# LED_STRIP.net
KiCad netlist of a schematic drawn in EAGLE
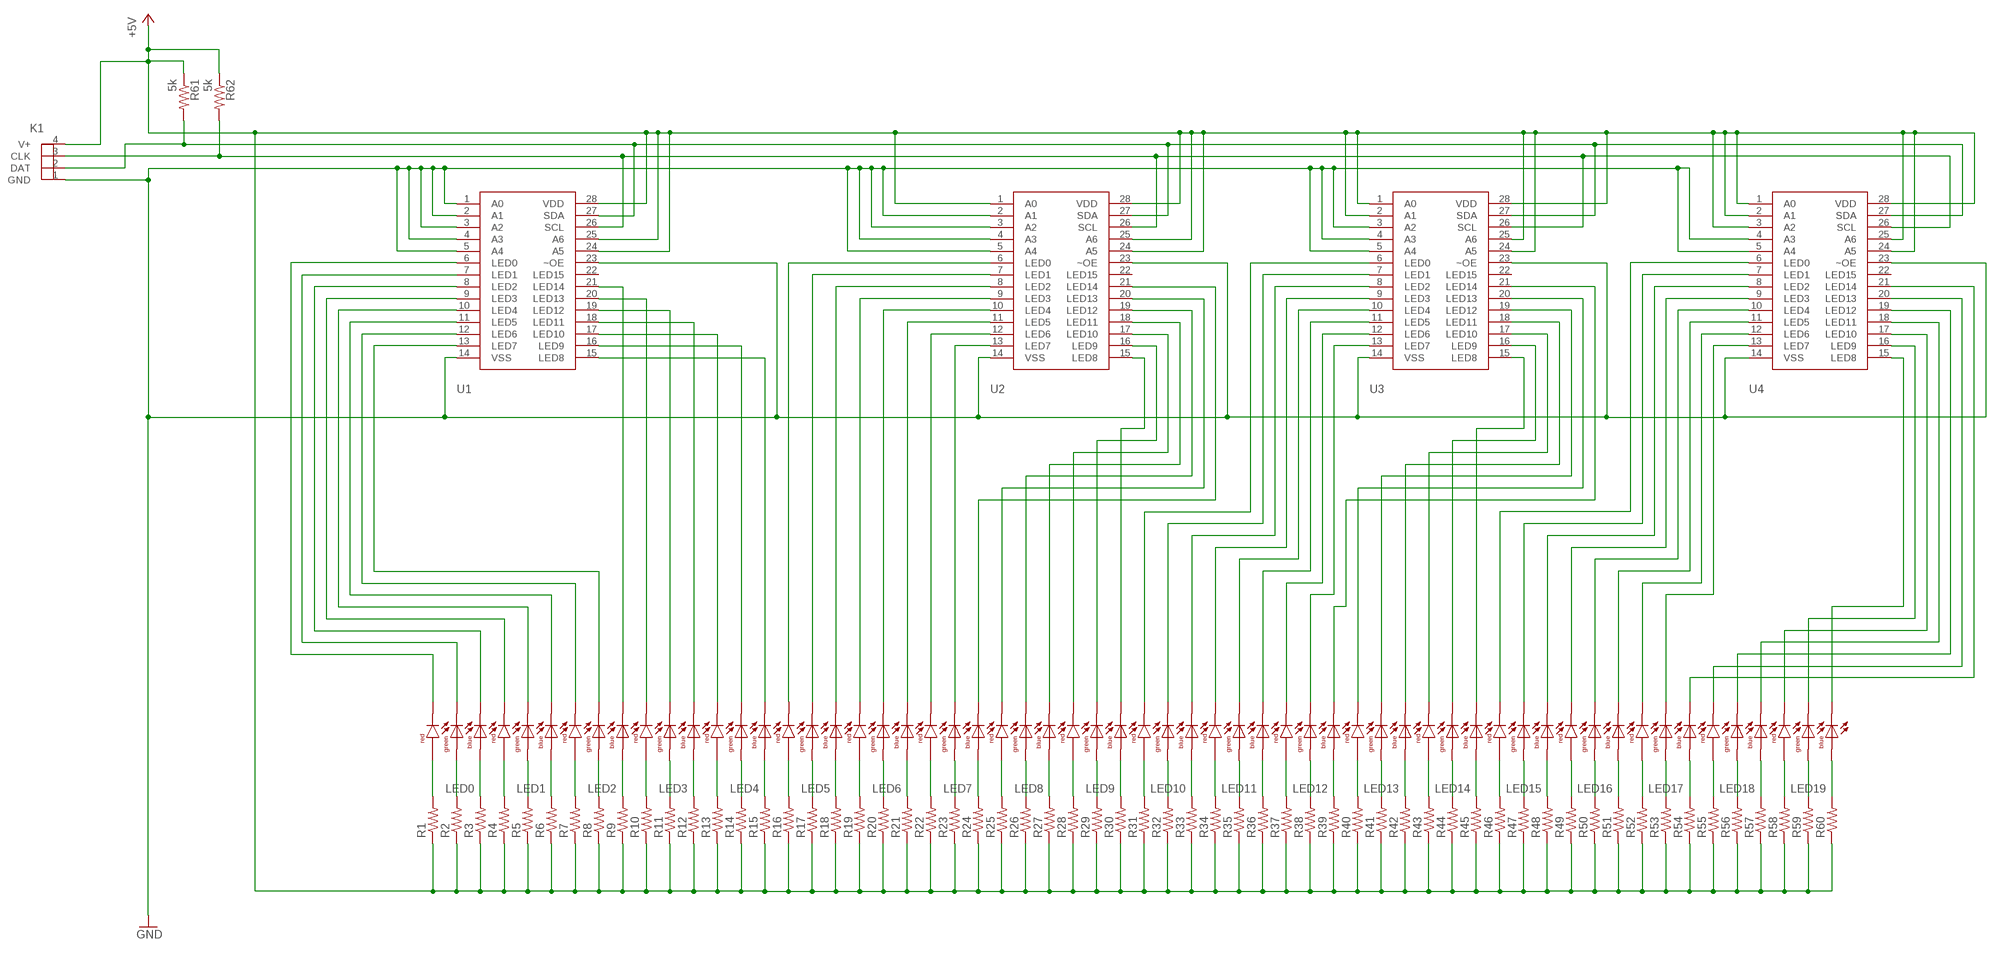
[diagram p0: schematic, sheet 1]

(export (version "E")
  (design (tool "Eeschema 10.0.6"))
  (components
    (comp (ref "K1")
      (value "LEDCONN")
      (footprint "eagle-import:4CONN")
      (libsource (lib "eagle-import") (part "LEDCONN"))
    )
    (comp (ref "LED0")
      (value "LED_RGB")
      (footprint "eagle-import:6-PLCC")
      (libsource (lib "eagle-import") (part "LED_RGB"))
    )
    (comp (ref "LED1")
      (value "LED_RGB")
      (footprint "eagle-import:6-PLCC")
      (libsource (lib "eagle-import") (part "LED_RGB"))
    )
    (comp (ref "LED2")
      (value "LED_RGB")
      (footprint "eagle-import:6-PLCC")
      (libsource (lib "eagle-import") (part "LED_RGB"))
    )
    (comp (ref "LED3")
      (value "LED_RGB")
      (footprint "eagle-import:6-PLCC")
      (libsource (lib "eagle-import") (part "LED_RGB"))
    )
    (comp (ref "LED4")
      (value "LED_RGB")
      (footprint "eagle-import:6-PLCC")
      (libsource (lib "eagle-import") (part "LED_RGB"))
    )
    (comp (ref "LED5")
      (value "LED_RGB")
      (footprint "eagle-import:6-PLCC")
      (libsource (lib "eagle-import") (part "LED_RGB"))
    )
    (comp (ref "LED6")
      (value "LED_RGB")
      (footprint "eagle-import:6-PLCC")
      (libsource (lib "eagle-import") (part "LED_RGB"))
    )
    (comp (ref "LED7")
      (value "LED_RGB")
      (footprint "eagle-import:6-PLCC")
      (libsource (lib "eagle-import") (part "LED_RGB"))
    )
    (comp (ref "LED8")
      (value "LED_RGB")
      (footprint "eagle-import:6-PLCC")
      (libsource (lib "eagle-import") (part "LED_RGB"))
    )
    (comp (ref "LED9")
      (value "LED_RGB")
      (footprint "eagle-import:6-PLCC")
      (libsource (lib "eagle-import") (part "LED_RGB"))
    )
    (comp (ref "LED10")
      (value "LED_RGB")
      (footprint "eagle-import:6-PLCC")
      (libsource (lib "eagle-import") (part "LED_RGB"))
    )
    (comp (ref "LED11")
      (value "LED_RGB")
      (footprint "eagle-import:6-PLCC")
      (libsource (lib "eagle-import") (part "LED_RGB"))
    )
    (comp (ref "LED12")
      (value "LED_RGB")
      (footprint "eagle-import:6-PLCC")
      (libsource (lib "eagle-import") (part "LED_RGB"))
    )
    (comp (ref "LED13")
      (value "LED_RGB")
      (footprint "eagle-import:6-PLCC")
      (libsource (lib "eagle-import") (part "LED_RGB"))
    )
    (comp (ref "LED14")
      (value "LED_RGB")
      (footprint "eagle-import:6-PLCC")
      (libsource (lib "eagle-import") (part "LED_RGB"))
    )
    (comp (ref "LED15")
      (value "LED_RGB")
      (footprint "eagle-import:6-PLCC")
      (libsource (lib "eagle-import") (part "LED_RGB"))
    )
    (comp (ref "LED16")
      (value "LED_RGB")
      (footprint "eagle-import:6-PLCC")
      (libsource (lib "eagle-import") (part "LED_RGB"))
    )
    (comp (ref "LED17")
      (value "LED_RGB")
      (footprint "eagle-import:6-PLCC")
      (libsource (lib "eagle-import") (part "LED_RGB"))
    )
    (comp (ref "LED18")
      (value "LED_RGB")
      (footprint "eagle-import:6-PLCC")
      (libsource (lib "eagle-import") (part "LED_RGB"))
    )
    (comp (ref "LED19")
      (value "LED_RGB")
      (footprint "eagle-import:6-PLCC")
      (libsource (lib "eagle-import") (part "LED_RGB"))
    )
    (comp (ref "R1")
      (value "R0402")
      (footprint "eagle-import:0402")
      (libsource (lib "eagle-import") (part "R0402"))
    )
    (comp (ref "R2")
      (value "R0402")
      (footprint "eagle-import:0402")
      (libsource (lib "eagle-import") (part "R0402"))
    )
    (comp (ref "R3")
      (value "R0402")
      (footprint "eagle-import:0402")
      (libsource (lib "eagle-import") (part "R0402"))
    )
    (comp (ref "R4")
      (value "R0402")
      (footprint "eagle-import:0402")
      (libsource (lib "eagle-import") (part "R0402"))
    )
    (comp (ref "R5")
      (value "R0402")
      (footprint "eagle-import:0402")
      (libsource (lib "eagle-import") (part "R0402"))
    )
    (comp (ref "R6")
      (value "R0402")
      (footprint "eagle-import:0402")
      (libsource (lib "eagle-import") (part "R0402"))
    )
    (comp (ref "R7")
      (value "R0402")
      (footprint "eagle-import:0402")
      (libsource (lib "eagle-import") (part "R0402"))
    )
    (comp (ref "R8")
      (value "R0402")
      (footprint "eagle-import:0402")
      (libsource (lib "eagle-import") (part "R0402"))
    )
    (comp (ref "R9")
      (value "R0402")
      (footprint "eagle-import:0402")
      (libsource (lib "eagle-import") (part "R0402"))
    )
    (comp (ref "R10")
      (value "R0402")
      (footprint "eagle-import:0402")
      (libsource (lib "eagle-import") (part "R0402"))
    )
    (comp (ref "R11")
      (value "R0402")
      (footprint "eagle-import:0402")
      (libsource (lib "eagle-import") (part "R0402"))
    )
    (comp (ref "R12")
      (value "R0402")
      (footprint "eagle-import:0402")
      (libsource (lib "eagle-import") (part "R0402"))
    )
    (comp (ref "R13")
      (value "R0402")
      (footprint "eagle-import:0402")
      (libsource (lib "eagle-import") (part "R0402"))
    )
    (comp (ref "R14")
      (value "R0402")
      (footprint "eagle-import:0402")
      (libsource (lib "eagle-import") (part "R0402"))
    )
    (comp (ref "R15")
      (value "R0402")
      (footprint "eagle-import:0402")
      (libsource (lib "eagle-import") (part "R0402"))
    )
    (comp (ref "R16")
      (value "R0402")
      (footprint "eagle-import:0402")
      (libsource (lib "eagle-import") (part "R0402"))
    )
    (comp (ref "R17")
      (value "R0402")
      (footprint "eagle-import:0402")
      (libsource (lib "eagle-import") (part "R0402"))
    )
    (comp (ref "R18")
      (value "R0402")
      (footprint "eagle-import:0402")
      (libsource (lib "eagle-import") (part "R0402"))
    )
    (comp (ref "R19")
      (value "R0402")
      (footprint "eagle-import:0402")
      (libsource (lib "eagle-import") (part "R0402"))
    )
    (comp (ref "R20")
      (value "R0402")
      (footprint "eagle-import:0402")
      (libsource (lib "eagle-import") (part "R0402"))
    )
    (comp (ref "R21")
      (value "R0402")
      (footprint "eagle-import:0402")
      (libsource (lib "eagle-import") (part "R0402"))
    )
    (comp (ref "R22")
      (value "R0402")
      (footprint "eagle-import:0402")
      (libsource (lib "eagle-import") (part "R0402"))
    )
    (comp (ref "R23")
      (value "R0402")
      (footprint "eagle-import:0402")
      (libsource (lib "eagle-import") (part "R0402"))
    )
    (comp (ref "R24")
      (value "R0402")
      (footprint "eagle-import:0402")
      (libsource (lib "eagle-import") (part "R0402"))
    )
    (comp (ref "R25")
      (value "R0402")
      (footprint "eagle-import:0402")
      (libsource (lib "eagle-import") (part "R0402"))
    )
    (comp (ref "R26")
      (value "R0402")
      (footprint "eagle-import:0402")
      (libsource (lib "eagle-import") (part "R0402"))
    )
    (comp (ref "R27")
      (value "R0402")
      (footprint "eagle-import:0402")
      (libsource (lib "eagle-import") (part "R0402"))
    )
    (comp (ref "R28")
      (value "R0402")
      (footprint "eagle-import:0402")
      (libsource (lib "eagle-import") (part "R0402"))
    )
    (comp (ref "R29")
      (value "R0402")
      (footprint "eagle-import:0402")
      (libsource (lib "eagle-import") (part "R0402"))
    )
    (comp (ref "R30")
      (value "R0402")
      (footprint "eagle-import:0402")
      (libsource (lib "eagle-import") (part "R0402"))
    )
    (comp (ref "R31")
      (value "R0402")
      (footprint "eagle-import:0402")
      (libsource (lib "eagle-import") (part "R0402"))
    )
    (comp (ref "R32")
      (value "R0402")
      (footprint "eagle-import:0402")
      (libsource (lib "eagle-import") (part "R0402"))
    )
    (comp (ref "R33")
      (value "R0402")
      (footprint "eagle-import:0402")
      (libsource (lib "eagle-import") (part "R0402"))
    )
    (comp (ref "R34")
      (value "R0402")
      (footprint "eagle-import:0402")
      (libsource (lib "eagle-import") (part "R0402"))
    )
    (comp (ref "R35")
      (value "R0402")
      (footprint "eagle-import:0402")
      (libsource (lib "eagle-import") (part "R0402"))
    )
    (comp (ref "R36")
      (value "R0402")
      (footprint "eagle-import:0402")
      (libsource (lib "eagle-import") (part "R0402"))
    )
    (comp (ref "R37")
      (value "R0402")
      (footprint "eagle-import:0402")
      (libsource (lib "eagle-import") (part "R0402"))
    )
    (comp (ref "R38")
      (value "R0402")
      (footprint "eagle-import:0402")
      (libsource (lib "eagle-import") (part "R0402"))
    )
    (comp (ref "R39")
      (value "R0402")
      (footprint "eagle-import:0402")
      (libsource (lib "eagle-import") (part "R0402"))
    )
    (comp (ref "R40")
      (value "R0402")
      (footprint "eagle-import:0402")
      (libsource (lib "eagle-import") (part "R0402"))
    )
    (comp (ref "R41")
      (value "R0402")
      (footprint "eagle-import:0402")
      (libsource (lib "eagle-import") (part "R0402"))
    )
    (comp (ref "R42")
      (value "R0402")
      (footprint "eagle-import:0402")
      (libsource (lib "eagle-import") (part "R0402"))
    )
    (comp (ref "R43")
      (value "R0402")
      (footprint "eagle-import:0402")
      (libsource (lib "eagle-import") (part "R0402"))
    )
    (comp (ref "R44")
      (value "R0402")
      (footprint "eagle-import:0402")
      (libsource (lib "eagle-import") (part "R0402"))
    )
    (comp (ref "R45")
      (value "R0402")
      (footprint "eagle-import:0402")
      (libsource (lib "eagle-import") (part "R0402"))
    )
    (comp (ref "R46")
      (value "R0402")
      (footprint "eagle-import:0402")
      (libsource (lib "eagle-import") (part "R0402"))
    )
    (comp (ref "R47")
      (value "R0402")
      (footprint "eagle-import:0402")
      (libsource (lib "eagle-import") (part "R0402"))
    )
    (comp (ref "R48")
      (value "R0402")
      (footprint "eagle-import:0402")
      (libsource (lib "eagle-import") (part "R0402"))
    )
    (comp (ref "R49")
      (value "R0402")
      (footprint "eagle-import:0402")
      (libsource (lib "eagle-import") (part "R0402"))
    )
    (comp (ref "R50")
      (value "R0402")
      (footprint "eagle-import:0402")
      (libsource (lib "eagle-import") (part "R0402"))
    )
    (comp (ref "R51")
      (value "R0402")
      (footprint "eagle-import:0402")
      (libsource (lib "eagle-import") (part "R0402"))
    )
    (comp (ref "R52")
      (value "R0402")
      (footprint "eagle-import:0402")
      (libsource (lib "eagle-import") (part "R0402"))
    )
    (comp (ref "R53")
      (value "R0402")
      (footprint "eagle-import:0402")
      (libsource (lib "eagle-import") (part "R0402"))
    )
    (comp (ref "R54")
      (value "R0402")
      (footprint "eagle-import:0402")
      (libsource (lib "eagle-import") (part "R0402"))
    )
    (comp (ref "R55")
      (value "R0402")
      (footprint "eagle-import:0402")
      (libsource (lib "eagle-import") (part "R0402"))
    )
    (comp (ref "R56")
      (value "R0402")
      (footprint "eagle-import:0402")
      (libsource (lib "eagle-import") (part "R0402"))
    )
    (comp (ref "R57")
      (value "R0402")
      (footprint "eagle-import:0402")
      (libsource (lib "eagle-import") (part "R0402"))
    )
    (comp (ref "R58")
      (value "R0402")
      (footprint "eagle-import:0402")
      (libsource (lib "eagle-import") (part "R0402"))
    )
    (comp (ref "R59")
      (value "R0402")
      (footprint "eagle-import:0402")
      (libsource (lib "eagle-import") (part "R0402"))
    )
    (comp (ref "R60")
      (value "R0402")
      (footprint "eagle-import:0402")
      (libsource (lib "eagle-import") (part "R0402"))
    )
    (comp (ref "R61")
      (value "5k")
      (footprint "eagle-import:0402")
      (libsource (lib "eagle-import") (part "R0402"))
    )
    (comp (ref "R62")
      (value "5k")
      (footprint "eagle-import:0402")
      (libsource (lib "eagle-import") (part "R0402"))
    )
    (comp (ref "U1")
      (value "PCA9635")
      (footprint "eagle-import:TSSOP28")
      (libsource (lib "eagle-import") (part "PCA9635"))
    )
    (comp (ref "U2")
      (value "PCA9635")
      (footprint "eagle-import:TSSOP28")
      (libsource (lib "eagle-import") (part "PCA9635"))
    )
    (comp (ref "U3")
      (value "PCA9635")
      (footprint "eagle-import:TSSOP28")
      (libsource (lib "eagle-import") (part "PCA9635"))
    )
    (comp (ref "U4")
      (value "PCA9635")
      (footprint "eagle-import:TSSOP28")
      (libsource (lib "eagle-import") (part "PCA9635"))
    )
  )
  (nets
    (net (code "1") (name "+5V") (class "Default")
      (node (ref "K1") (pin "4") (pinfunction "V+_4") (pintype "bidirectional"))
      (node (ref "R1") (pin "P$1") (pinfunction "1_P$1") (pintype "passive"))
      (node (ref "R10") (pin "P$1") (pinfunction "1_P$1") (pintype "passive"))
      (node (ref "R11") (pin "P$1") (pinfunction "1_P$1") (pintype "passive"))
      (node (ref "R12") (pin "P$1") (pinfunction "1_P$1") (pintype "passive"))
      (node (ref "R13") (pin "P$1") (pinfunction "1_P$1") (pintype "passive"))
      (node (ref "R14") (pin "P$1") (pinfunction "1_P$1") (pintype "passive"))
      (node (ref "R15") (pin "P$1") (pinfunction "1_P$1") (pintype "passive"))
      (node (ref "R16") (pin "P$1") (pinfunction "1_P$1") (pintype "passive"))
      (node (ref "R17") (pin "P$1") (pinfunction "1_P$1") (pintype "passive"))
      (node (ref "R18") (pin "P$1") (pinfunction "1_P$1") (pintype "passive"))
      (node (ref "R19") (pin "P$1") (pinfunction "1_P$1") (pintype "passive"))
      (node (ref "R2") (pin "P$1") (pinfunction "1_P$1") (pintype "passive"))
      (node (ref "R20") (pin "P$1") (pinfunction "1_P$1") (pintype "passive"))
      (node (ref "R21") (pin "P$1") (pinfunction "1_P$1") (pintype "passive"))
      (node (ref "R22") (pin "P$1") (pinfunction "1_P$1") (pintype "passive"))
      (node (ref "R23") (pin "P$1") (pinfunction "1_P$1") (pintype "passive"))
      (node (ref "R24") (pin "P$1") (pinfunction "1_P$1") (pintype "passive"))
      (node (ref "R25") (pin "P$1") (pinfunction "1_P$1") (pintype "passive"))
      (node (ref "R26") (pin "P$1") (pinfunction "1_P$1") (pintype "passive"))
      (node (ref "R27") (pin "P$1") (pinfunction "1_P$1") (pintype "passive"))
      (node (ref "R28") (pin "P$1") (pinfunction "1_P$1") (pintype "passive"))
      (node (ref "R29") (pin "P$1") (pinfunction "1_P$1") (pintype "passive"))
      (node (ref "R3") (pin "P$1") (pinfunction "1_P$1") (pintype "passive"))
      (node (ref "R30") (pin "P$1") (pinfunction "1_P$1") (pintype "passive"))
      (node (ref "R31") (pin "P$1") (pinfunction "1_P$1") (pintype "passive"))
      (node (ref "R32") (pin "P$1") (pinfunction "1_P$1") (pintype "passive"))
      (node (ref "R33") (pin "P$1") (pinfunction "1_P$1") (pintype "passive"))
      (node (ref "R34") (pin "P$1") (pinfunction "1_P$1") (pintype "passive"))
      (node (ref "R35") (pin "P$1") (pinfunction "1_P$1") (pintype "passive"))
      (node (ref "R36") (pin "P$1") (pinfunction "1_P$1") (pintype "passive"))
      (node (ref "R37") (pin "P$1") (pinfunction "1_P$1") (pintype "passive"))
      (node (ref "R38") (pin "P$1") (pinfunction "1_P$1") (pintype "passive"))
      (node (ref "R39") (pin "P$1") (pinfunction "1_P$1") (pintype "passive"))
      (node (ref "R4") (pin "P$1") (pinfunction "1_P$1") (pintype "passive"))
      (node (ref "R40") (pin "P$1") (pinfunction "1_P$1") (pintype "passive"))
      (node (ref "R41") (pin "P$1") (pinfunction "1_P$1") (pintype "passive"))
      (node (ref "R42") (pin "P$1") (pinfunction "1_P$1") (pintype "passive"))
      (node (ref "R43") (pin "P$1") (pinfunction "1_P$1") (pintype "passive"))
      (node (ref "R44") (pin "P$1") (pinfunction "1_P$1") (pintype "passive"))
      (node (ref "R45") (pin "P$1") (pinfunction "1_P$1") (pintype "passive"))
      (node (ref "R46") (pin "P$1") (pinfunction "1_P$1") (pintype "passive"))
      (node (ref "R47") (pin "P$1") (pinfunction "1_P$1") (pintype "passive"))
      (node (ref "R48") (pin "P$1") (pinfunction "1_P$1") (pintype "passive"))
      (node (ref "R49") (pin "P$1") (pinfunction "1_P$1") (pintype "passive"))
      (node (ref "R5") (pin "P$1") (pinfunction "1_P$1") (pintype "passive"))
      (node (ref "R50") (pin "P$1") (pinfunction "1_P$1") (pintype "passive"))
      (node (ref "R51") (pin "P$1") (pinfunction "1_P$1") (pintype "passive"))
      (node (ref "R52") (pin "P$1") (pinfunction "1_P$1") (pintype "passive"))
      (node (ref "R53") (pin "P$1") (pinfunction "1_P$1") (pintype "passive"))
      (node (ref "R54") (pin "P$1") (pinfunction "1_P$1") (pintype "passive"))
      (node (ref "R55") (pin "P$1") (pinfunction "1_P$1") (pintype "passive"))
      (node (ref "R56") (pin "P$1") (pinfunction "1_P$1") (pintype "passive"))
      (node (ref "R57") (pin "P$1") (pinfunction "1_P$1") (pintype "passive"))
      (node (ref "R58") (pin "P$1") (pinfunction "1_P$1") (pintype "passive"))
      (node (ref "R59") (pin "P$1") (pinfunction "1_P$1") (pintype "passive"))
      (node (ref "R6") (pin "P$1") (pinfunction "1_P$1") (pintype "passive"))
      (node (ref "R60") (pin "P$1") (pinfunction "1_P$1") (pintype "passive"))
      (node (ref "R61") (pin "P$1") (pinfunction "1_P$1") (pintype "passive"))
      (node (ref "R62") (pin "P$1") (pinfunction "1_P$1") (pintype "passive"))
      (node (ref "R7") (pin "P$1") (pinfunction "1_P$1") (pintype "passive"))
      (node (ref "R8") (pin "P$1") (pinfunction "1_P$1") (pintype "passive"))
      (node (ref "R9") (pin "P$1") (pinfunction "1_P$1") (pintype "passive"))
      (node (ref "U1") (pin "24") (pinfunction "A5_24") (pintype "bidirectional"))
      (node (ref "U1") (pin "25") (pinfunction "A6_25") (pintype "bidirectional"))
      (node (ref "U1") (pin "28") (pinfunction "VDD_28") (pintype "bidirectional"))
      (node (ref "U2") (pin "1") (pinfunction "A0_1") (pintype "bidirectional"))
      (node (ref "U2") (pin "24") (pinfunction "A5_24") (pintype "bidirectional"))
      (node (ref "U2") (pin "25") (pinfunction "A6_25") (pintype "bidirectional"))
      (node (ref "U2") (pin "28") (pinfunction "VDD_28") (pintype "bidirectional"))
      (node (ref "U3") (pin "1") (pinfunction "A0_1") (pintype "bidirectional"))
      (node (ref "U3") (pin "2") (pinfunction "A1_2") (pintype "bidirectional"))
      (node (ref "U3") (pin "24") (pinfunction "A5_24") (pintype "bidirectional"))
      (node (ref "U3") (pin "25") (pinfunction "A6_25") (pintype "bidirectional"))
      (node (ref "U3") (pin "28") (pinfunction "VDD_28") (pintype "bidirectional"))
      (node (ref "U4") (pin "1") (pinfunction "A0_1") (pintype "bidirectional"))
      (node (ref "U4") (pin "2") (pinfunction "A1_2") (pintype "bidirectional"))
      (node (ref "U4") (pin "24") (pinfunction "A5_24") (pintype "bidirectional"))
      (node (ref "U4") (pin "25") (pinfunction "A6_25") (pintype "bidirectional"))
      (node (ref "U4") (pin "28") (pinfunction "VDD_28") (pintype "bidirectional"))
      (node (ref "U4") (pin "3") (pinfunction "A2_3") (pintype "bidirectional"))
    )
    (net (code "2") (name "GND") (class "Default")
      (node (ref "K1") (pin "1") (pinfunction "GND_1") (pintype "bidirectional"))
      (node (ref "U1") (pin "1") (pinfunction "A0_1") (pintype "bidirectional"))
      (node (ref "U1") (pin "14") (pinfunction "VSS_14") (pintype "bidirectional"))
      (node (ref "U1") (pin "2") (pinfunction "A1_2") (pintype "bidirectional"))
      (node (ref "U1") (pin "23") (pinfunction "~{OE}_23") (pintype "bidirectional"))
      (node (ref "U1") (pin "3") (pinfunction "A2_3") (pintype "bidirectional"))
      (node (ref "U1") (pin "4") (pinfunction "A3_4") (pintype "bidirectional"))
      (node (ref "U1") (pin "5") (pinfunction "A4_5") (pintype "bidirectional"))
      (node (ref "U2") (pin "14") (pinfunction "VSS_14") (pintype "bidirectional"))
      (node (ref "U2") (pin "2") (pinfunction "A1_2") (pintype "bidirectional"))
      (node (ref "U2") (pin "23") (pinfunction "~{OE}_23") (pintype "bidirectional"))
      (node (ref "U2") (pin "3") (pinfunction "A2_3") (pintype "bidirectional"))
      (node (ref "U2") (pin "4") (pinfunction "A3_4") (pintype "bidirectional"))
      (node (ref "U2") (pin "5") (pinfunction "A4_5") (pintype "bidirectional"))
      (node (ref "U3") (pin "14") (pinfunction "VSS_14") (pintype "bidirectional"))
      (node (ref "U3") (pin "23") (pinfunction "~{OE}_23") (pintype "bidirectional"))
      (node (ref "U3") (pin "3") (pinfunction "A2_3") (pintype "bidirectional"))
      (node (ref "U3") (pin "4") (pinfunction "A3_4") (pintype "bidirectional"))
      (node (ref "U3") (pin "5") (pinfunction "A4_5") (pintype "bidirectional"))
      (node (ref "U4") (pin "14") (pinfunction "VSS_14") (pintype "bidirectional"))
      (node (ref "U4") (pin "23") (pinfunction "~{OE}_23") (pintype "bidirectional"))
      (node (ref "U4") (pin "4") (pinfunction "A3_4") (pintype "bidirectional"))
      (node (ref "U4") (pin "5") (pinfunction "A4_5") (pintype "bidirectional"))
    )
    (net (code "3") (name "Net-(K1-CLK)") (class "Default")
      (node (ref "K1") (pin "3") (pinfunction "CLK_3") (pintype "bidirectional"))
      (node (ref "R62") (pin "P$2") (pinfunction "2_P$2") (pintype "passive"))
      (node (ref "U1") (pin "26") (pinfunction "SCL_26") (pintype "bidirectional"))
      (node (ref "U2") (pin "26") (pinfunction "SCL_26") (pintype "bidirectional"))
      (node (ref "U3") (pin "26") (pinfunction "SCL_26") (pintype "bidirectional"))
      (node (ref "U4") (pin "26") (pinfunction "SCL_26") (pintype "bidirectional"))
    )
    (net (code "4") (name "Net-(K1-DAT)") (class "Default")
      (node (ref "K1") (pin "2") (pinfunction "DAT_2") (pintype "bidirectional"))
      (node (ref "R61") (pin "P$2") (pinfunction "2_P$2") (pintype "passive"))
      (node (ref "U1") (pin "27") (pinfunction "SDA_27") (pintype "bidirectional"))
      (node (ref "U2") (pin "27") (pinfunction "SDA_27") (pintype "bidirectional"))
      (node (ref "U3") (pin "27") (pinfunction "SDA_27") (pintype "bidirectional"))
      (node (ref "U4") (pin "27") (pinfunction "SDA_27") (pintype "bidirectional"))
    )
    (net (code "5") (name "Net-(R1-2)") (class "Default")
      (node (ref "LED0") (pin "RED_HIGH") (pinfunction "RED_HIGH_RED_HIGH") (pintype "passive"))
      (node (ref "R1") (pin "P$2") (pinfunction "2_P$2") (pintype "passive"))
    )
    (net (code "6") (name "Net-(R2-2)") (class "Default")
      (node (ref "LED0") (pin "GREEN_HIGH") (pinfunction "GREEN_HIGH_GREEN_HIGH") (pintype "passive"))
      (node (ref "R2") (pin "P$2") (pinfunction "2_P$2") (pintype "passive"))
    )
    (net (code "7") (name "Net-(R3-2)") (class "Default")
      (node (ref "LED0") (pin "BLUE_HIGH") (pinfunction "BLUE_HIGH_BLUE_HIGH") (pintype "passive"))
      (node (ref "R3") (pin "P$2") (pinfunction "2_P$2") (pintype "passive"))
    )
    (net (code "8") (name "Net-(R4-2)") (class "Default")
      (node (ref "LED1") (pin "RED_HIGH") (pinfunction "RED_HIGH_RED_HIGH") (pintype "passive"))
      (node (ref "R4") (pin "P$2") (pinfunction "2_P$2") (pintype "passive"))
    )
    (net (code "9") (name "Net-(R5-2)") (class "Default")
      (node (ref "LED1") (pin "GREEN_HIGH") (pinfunction "GREEN_HIGH_GREEN_HIGH") (pintype "passive"))
      (node (ref "R5") (pin "P$2") (pinfunction "2_P$2") (pintype "passive"))
    )
    (net (code "10") (name "Net-(R6-2)") (class "Default")
      (node (ref "LED1") (pin "BLUE_HIGH") (pinfunction "BLUE_HIGH_BLUE_HIGH") (pintype "passive"))
      (node (ref "R6") (pin "P$2") (pinfunction "2_P$2") (pintype "passive"))
    )
    (net (code "11") (name "Net-(R7-2)") (class "Default")
      (node (ref "LED2") (pin "RED_HIGH") (pinfunction "RED_HIGH_RED_HIGH") (pintype "passive"))
      (node (ref "R7") (pin "P$2") (pinfunction "2_P$2") (pintype "passive"))
    )
    (net (code "12") (name "Net-(R8-2)") (class "Default")
      (node (ref "LED2") (pin "GREEN_HIGH") (pinfunction "GREEN_HIGH_GREEN_HIGH") (pintype "passive"))
      (node (ref "R8") (pin "P$2") (pinfunction "2_P$2") (pintype "passive"))
    )
    (net (code "13") (name "Net-(R9-2)") (class "Default")
      (node (ref "LED2") (pin "BLUE_HIGH") (pinfunction "BLUE_HIGH_BLUE_HIGH") (pintype "passive"))
      (node (ref "R9") (pin "P$2") (pinfunction "2_P$2") (pintype "passive"))
    )
    (net (code "14") (name "Net-(R10-2)") (class "Default")
      (node (ref "LED3") (pin "RED_HIGH") (pinfunction "RED_HIGH_RED_HIGH") (pintype "passive"))
      (node (ref "R10") (pin "P$2") (pinfunction "2_P$2") (pintype "passive"))
    )
    (net (code "15") (name "Net-(R11-2)") (class "Default")
      (node (ref "LED3") (pin "GREEN_HIGH") (pinfunction "GREEN_HIGH_GREEN_HIGH") (pintype "passive"))
      (node (ref "R11") (pin "P$2") (pinfunction "2_P$2") (pintype "passive"))
    )
    (net (code "16") (name "Net-(R12-2)") (class "Default")
      (node (ref "LED3") (pin "BLUE_HIGH") (pinfunction "BLUE_HIGH_BLUE_HIGH") (pintype "passive"))
      (node (ref "R12") (pin "P$2") (pinfunction "2_P$2") (pintype "passive"))
    )
    (net (code "17") (name "Net-(R13-2)") (class "Default")
      (node (ref "LED4") (pin "RED_HIGH") (pinfunction "RED_HIGH_RED_HIGH") (pintype "passive"))
      (node (ref "R13") (pin "P$2") (pinfunction "2_P$2") (pintype "passive"))
    )
    (net (code "18") (name "Net-(R14-2)") (class "Default")
      (node (ref "LED4") (pin "GREEN_HIGH") (pinfunction "GREEN_HIGH_GREEN_HIGH") (pintype "passive"))
      (node (ref "R14") (pin "P$2") (pinfunction "2_P$2") (pintype "passive"))
    )
    (net (code "19") (name "Net-(R15-2)") (class "Default")
      (node (ref "LED4") (pin "BLUE_HIGH") (pinfunction "BLUE_HIGH_BLUE_HIGH") (pintype "passive"))
      (node (ref "R15") (pin "P$2") (pinfunction "2_P$2") (pintype "passive"))
    )
    (net (code "20") (name "Net-(R16-2)") (class "Default")
      (node (ref "LED5") (pin "RED_HIGH") (pinfunction "RED_HIGH_RED_HIGH") (pintype "passive"))
      (node (ref "R16") (pin "P$2") (pinfunction "2_P$2") (pintype "passive"))
    )
    (net (code "21") (name "Net-(R17-2)") (class "Default")
      (node (ref "LED5") (pin "GREEN_HIGH") (pinfunction "GREEN_HIGH_GREEN_HIGH") (pintype "passive"))
      (node (ref "R17") (pin "P$2") (pinfunction "2_P$2") (pintype "passive"))
    )
    (net (code "22") (name "Net-(R18-2)") (class "Default")
      (node (ref "LED5") (pin "BLUE_HIGH") (pinfunction "BLUE_HIGH_BLUE_HIGH") (pintype "passive"))
      (node (ref "R18") (pin "P$2") (pinfunction "2_P$2") (pintype "passive"))
    )
    (net (code "23") (name "Net-(R19-2)") (class "Default")
      (node (ref "LED6") (pin "RED_HIGH") (pinfunction "RED_HIGH_RED_HIGH") (pintype "passive"))
      (node (ref "R19") (pin "P$2") (pinfunction "2_P$2") (pintype "passive"))
    )
    (net (code "24") (name "Net-(R20-2)") (class "Default")
      (node (ref "LED6") (pin "GREEN_HIGH") (pinfunction "GREEN_HIGH_GREEN_HIGH") (pintype "passive"))
      (node (ref "R20") (pin "P$2") (pinfunction "2_P$2") (pintype "passive"))
    )
    (net (code "25") (name "Net-(R21-2)") (class "Default")
      (node (ref "LED6") (pin "BLUE_HIGH") (pinfunction "BLUE_HIGH_BLUE_HIGH") (pintype "passive"))
      (node (ref "R21") (pin "P$2") (pinfunction "2_P$2") (pintype "passive"))
    )
    (net (code "26") (name "Net-(R22-2)") (class "Default")
      (node (ref "LED7") (pin "RED_HIGH") (pinfunction "RED_HIGH_RED_HIGH") (pintype "passive"))
      (node (ref "R22") (pin "P$2") (pinfunction "2_P$2") (pintype "passive"))
    )
    (net (code "27") (name "Net-(R23-2)") (class "Default")
      (node (ref "LED7") (pin "GREEN_HIGH") (pinfunction "GREEN_HIGH_GREEN_HIGH") (pintype "passive"))
      (node (ref "R23") (pin "P$2") (pinfunction "2_P$2") (pintype "passive"))
    )
    (net (code "28") (name "Net-(R24-2)") (class "Default")
      (node (ref "LED7") (pin "BLUE_HIGH") (pinfunction "BLUE_HIGH_BLUE_HIGH") (pintype "passive"))
      (node (ref "R24") (pin "P$2") (pinfunction "2_P$2") (pintype "passive"))
    )
    (net (code "29") (name "Net-(R25-2)") (class "Default")
      (node (ref "LED8") (pin "RED_HIGH") (pinfunction "RED_HIGH_RED_HIGH") (pintype "passive"))
      (node (ref "R25") (pin "P$2") (pinfunction "2_P$2") (pintype "passive"))
    )
    (net (code "30") (name "Net-(R26-2)") (class "Default")
      (node (ref "LED8") (pin "GREEN_HIGH") (pinfunction "GREEN_HIGH_GREEN_HIGH") (pintype "passive"))
      (node (ref "R26") (pin "P$2") (pinfunction "2_P$2") (pintype "passive"))
    )
    (net (code "31") (name "Net-(R27-2)") (class "Default")
      (node (ref "LED8") (pin "BLUE_HIGH") (pinfunction "BLUE_HIGH_BLUE_HIGH") (pintype "passive"))
      (node (ref "R27") (pin "P$2") (pinfunction "2_P$2") (pintype "passive"))
    )
    (net (code "32") (name "Net-(R28-2)") (class "Default")
      (node (ref "LED9") (pin "RED_HIGH") (pinfunction "RED_HIGH_RED_HIGH") (pintype "passive"))
      (node (ref "R28") (pin "P$2") (pinfunction "2_P$2") (pintype "passive"))
    )
    (net (code "33") (name "Net-(R29-2)") (class "Default")
      (node (ref "LED9") (pin "GREEN_HIGH") (pinfunction "GREEN_HIGH_GREEN_HIGH") (pintype "passive"))
      (node (ref "R29") (pin "P$2") (pinfunction "2_P$2") (pintype "passive"))
    )
    (net (code "34") (name "Net-(R30-2)") (class "Default")
      (node (ref "LED9") (pin "BLUE_HIGH") (pinfunction "BLUE_HIGH_BLUE_HIGH") (pintype "passive"))
      (node (ref "R30") (pin "P$2") (pinfunction "2_P$2") (pintype "passive"))
    )
    (net (code "35") (name "Net-(R31-2)") (class "Default")
      (node (ref "LED10") (pin "RED_HIGH") (pinfunction "RED_HIGH_RED_HIGH") (pintype "passive"))
      (node (ref "R31") (pin "P$2") (pinfunction "2_P$2") (pintype "passive"))
    )
    (net (code "36") (name "Net-(R32-2)") (class "Default")
      (node (ref "LED10") (pin "GREEN_HIGH") (pinfunction "GREEN_HIGH_GREEN_HIGH") (pintype "passive"))
      (node (ref "R32") (pin "P$2") (pinfunction "2_P$2") (pintype "passive"))
    )
    (net (code "37") (name "Net-(R33-2)") (class "Default")
      (node (ref "LED10") (pin "BLUE_HIGH") (pinfunction "BLUE_HIGH_BLUE_HIGH") (pintype "passive"))
      (node (ref "R33") (pin "P$2") (pinfunction "2_P$2") (pintype "passive"))
    )
    (net (code "38") (name "Net-(R34-2)") (class "Default")
      (node (ref "LED11") (pin "RED_HIGH") (pinfunction "RED_HIGH_RED_HIGH") (pintype "passive"))
      (node (ref "R34") (pin "P$2") (pinfunction "2_P$2") (pintype "passive"))
    )
    (net (code "39") (name "Net-(R35-2)") (class "Default")
      (node (ref "LED11") (pin "GREEN_HIGH") (pinfunction "GREEN_HIGH_GREEN_HIGH") (pintype "passive"))
      (node (ref "R35") (pin "P$2") (pinfunction "2_P$2") (pintype "passive"))
    )
    (net (code "40") (name "Net-(R36-2)") (class "Default")
      (node (ref "LED11") (pin "BLUE_HIGH") (pinfunction "BLUE_HIGH_BLUE_HIGH") (pintype "passive"))
      (node (ref "R36") (pin "P$2") (pinfunction "2_P$2") (pintype "passive"))
    )
    (net (code "41") (name "Net-(R37-2)") (class "Default")
      (node (ref "LED12") (pin "RED_HIGH") (pinfunction "RED_HIGH_RED_HIGH") (pintype "passive"))
      (node (ref "R37") (pin "P$2") (pinfunction "2_P$2") (pintype "passive"))
    )
    (net (code "42") (name "Net-(R38-2)") (class "Default")
      (node (ref "LED12") (pin "GREEN_HIGH") (pinfunction "GREEN_HIGH_GREEN_HIGH") (pintype "passive"))
      (node (ref "R38") (pin "P$2") (pinfunction "2_P$2") (pintype "passive"))
    )
    (net (code "43") (name "Net-(R39-2)") (class "Default")
      (node (ref "LED12") (pin "BLUE_HIGH") (pinfunction "BLUE_HIGH_BLUE_HIGH") (pintype "passive"))
      (node (ref "R39") (pin "P$2") (pinfunction "2_P$2") (pintype "passive"))
    )
    (net (code "44") (name "Net-(R40-2)") (class "Default")
      (node (ref "LED13") (pin "RED_HIGH") (pinfunction "RED_HIGH_RED_HIGH") (pintype "passive"))
      (node (ref "R40") (pin "P$2") (pinfunction "2_P$2") (pintype "passive"))
    )
    (net (code "45") (name "Net-(R41-2)") (class "Default")
      (node (ref "LED13") (pin "GREEN_HIGH") (pinfunction "GREEN_HIGH_GREEN_HIGH") (pintype "passive"))
      (node (ref "R41") (pin "P$2") (pinfunction "2_P$2") (pintype "passive"))
    )
    (net (code "46") (name "Net-(R42-2)") (class "Default")
      (node (ref "LED13") (pin "BLUE_HIGH") (pinfunction "BLUE_HIGH_BLUE_HIGH") (pintype "passive"))
      (node (ref "R42") (pin "P$2") (pinfunction "2_P$2") (pintype "passive"))
    )
    (net (code "47") (name "Net-(R43-2)") (class "Default")
      (node (ref "LED14") (pin "RED_HIGH") (pinfunction "RED_HIGH_RED_HIGH") (pintype "passive"))
      (node (ref "R43") (pin "P$2") (pinfunction "2_P$2") (pintype "passive"))
    )
    (net (code "48") (name "Net-(R44-2)") (class "Default")
      (node (ref "LED14") (pin "GREEN_HIGH") (pinfunction "GREEN_HIGH_GREEN_HIGH") (pintype "passive"))
      (node (ref "R44") (pin "P$2") (pinfunction "2_P$2") (pintype "passive"))
    )
    (net (code "49") (name "Net-(R45-2)") (class "Default")
      (node (ref "LED14") (pin "BLUE_HIGH") (pinfunction "BLUE_HIGH_BLUE_HIGH") (pintype "passive"))
      (node (ref "R45") (pin "P$2") (pinfunction "2_P$2") (pintype "passive"))
    )
    (net (code "50") (name "Net-(R46-2)") (class "Default")
      (node (ref "LED15") (pin "RED_HIGH") (pinfunction "RED_HIGH_RED_HIGH") (pintype "passive"))
      (node (ref "R46") (pin "P$2") (pinfunction "2_P$2") (pintype "passive"))
    )
    (net (code "51") (name "Net-(R47-2)") (class "Default")
      (node (ref "LED15") (pin "GREEN_HIGH") (pinfunction "GREEN_HIGH_GREEN_HIGH") (pintype "passive"))
      (node (ref "R47") (pin "P$2") (pinfunction "2_P$2") (pintype "passive"))
    )
    (net (code "52") (name "Net-(R48-2)") (class "Default")
      (node (ref "LED15") (pin "BLUE_HIGH") (pinfunction "BLUE_HIGH_BLUE_HIGH") (pintype "passive"))
      (node (ref "R48") (pin "P$2") (pinfunction "2_P$2") (pintype "passive"))
    )
    (net (code "53") (name "Net-(R49-2)") (class "Default")
      (node (ref "LED16") (pin "RED_HIGH") (pinfunction "RED_HIGH_RED_HIGH") (pintype "passive"))
      (node (ref "R49") (pin "P$2") (pinfunction "2_P$2") (pintype "passive"))
    )
    (net (code "54") (name "Net-(R50-2)") (class "Default")
      (node (ref "LED16") (pin "GREEN_HIGH") (pinfunction "GREEN_HIGH_GREEN_HIGH") (pintype "passive"))
      (node (ref "R50") (pin "P$2") (pinfunction "2_P$2") (pintype "passive"))
    )
    (net (code "55") (name "Net-(R51-2)") (class "Default")
      (node (ref "LED16") (pin "BLUE_HIGH") (pinfunction "BLUE_HIGH_BLUE_HIGH") (pintype "passive"))
      (node (ref "R51") (pin "P$2") (pinfunction "2_P$2") (pintype "passive"))
    )
    (net (code "56") (name "Net-(R52-2)") (class "Default")
      (node (ref "LED17") (pin "RED_HIGH") (pinfunction "RED_HIGH_RED_HIGH") (pintype "passive"))
      (node (ref "R52") (pin "P$2") (pinfunction "2_P$2") (pintype "passive"))
    )
    (net (code "57") (name "Net-(R53-2)") (class "Default")
      (node (ref "LED17") (pin "GREEN_HIGH") (pinfunction "GREEN_HIGH_GREEN_HIGH") (pintype "passive"))
      (node (ref "R53") (pin "P$2") (pinfunction "2_P$2") (pintype "passive"))
    )
    (net (code "58") (name "Net-(R54-2)") (class "Default")
      (node (ref "LED17") (pin "BLUE_HIGH") (pinfunction "BLUE_HIGH_BLUE_HIGH") (pintype "passive"))
      (node (ref "R54") (pin "P$2") (pinfunction "2_P$2") (pintype "passive"))
    )
    (net (code "59") (name "Net-(R55-2)") (class "Default")
      (node (ref "LED18") (pin "RED_HIGH") (pinfunction "RED_HIGH_RED_HIGH") (pintype "passive"))
      (node (ref "R55") (pin "P$2") (pinfunction "2_P$2") (pintype "passive"))
    )
    (net (code "60") (name "Net-(R56-2)") (class "Default")
      (node (ref "LED18") (pin "GREEN_HIGH") (pinfunction "GREEN_HIGH_GREEN_HIGH") (pintype "passive"))
      (node (ref "R56") (pin "P$2") (pinfunction "2_P$2") (pintype "passive"))
    )
    (net (code "61") (name "Net-(R57-2)") (class "Default")
      (node (ref "LED18") (pin "BLUE_HIGH") (pinfunction "BLUE_HIGH_BLUE_HIGH") (pintype "passive"))
      (node (ref "R57") (pin "P$2") (pinfunction "2_P$2") (pintype "passive"))
    )
    (net (code "62") (name "Net-(R58-2)") (class "Default")
      (node (ref "LED19") (pin "RED_HIGH") (pinfunction "RED_HIGH_RED_HIGH") (pintype "passive"))
      (node (ref "R58") (pin "P$2") (pinfunction "2_P$2") (pintype "passive"))
    )
    (net (code "63") (name "Net-(R59-2)") (class "Default")
      (node (ref "LED19") (pin "GREEN_HIGH") (pinfunction "GREEN_HIGH_GREEN_HIGH") (pintype "passive"))
      (node (ref "R59") (pin "P$2") (pinfunction "2_P$2") (pintype "passive"))
    )
    (net (code "64") (name "Net-(R60-2)") (class "Default")
      (node (ref "LED19") (pin "BLUE_HIGH") (pinfunction "BLUE_HIGH_BLUE_HIGH") (pintype "passive"))
      (node (ref "R60") (pin "P$2") (pinfunction "2_P$2") (pintype "passive"))
    )
    (net (code "65") (name "Net-(U1-LED0)") (class "Default")
      (node (ref "LED0") (pin "RED_LOW") (pinfunction "RED_LOW_RED_LOW") (pintype "passive"))
      (node (ref "U1") (pin "6") (pinfunction "LED0_6") (pintype "bidirectional"))
    )
    (net (code "66") (name "Net-(U1-LED1)") (class "Default")
      (node (ref "LED0") (pin "GREEN_LOW") (pinfunction "GREEN_LOW_GREEN_LOW") (pintype "passive"))
      (node (ref "U1") (pin "7") (pinfunction "LED1_7") (pintype "bidirectional"))
    )
    (net (code "67") (name "Net-(U1-LED2)") (class "Default")
      (node (ref "LED0") (pin "BLUE_LOW") (pinfunction "BLUE_LOW_BLUE_LOW") (pintype "passive"))
      (node (ref "U1") (pin "8") (pinfunction "LED2_8") (pintype "bidirectional"))
    )
    (net (code "68") (name "Net-(U1-LED3)") (class "Default")
      (node (ref "LED1") (pin "RED_LOW") (pinfunction "RED_LOW_RED_LOW") (pintype "passive"))
      (node (ref "U1") (pin "9") (pinfunction "LED3_9") (pintype "bidirectional"))
    )
    (net (code "69") (name "Net-(U1-LED4)") (class "Default")
      (node (ref "LED1") (pin "GREEN_LOW") (pinfunction "GREEN_LOW_GREEN_LOW") (pintype "passive"))
      (node (ref "U1") (pin "10") (pinfunction "LED4_10") (pintype "bidirectional"))
    )
    (net (code "70") (name "Net-(U1-LED5)") (class "Default")
      (node (ref "LED1") (pin "BLUE_LOW") (pinfunction "BLUE_LOW_BLUE_LOW") (pintype "passive"))
      (node (ref "U1") (pin "11") (pinfunction "LED5_11") (pintype "bidirectional"))
    )
    (net (code "71") (name "Net-(U1-LED6)") (class "Default")
      (node (ref "LED2") (pin "RED_LOW") (pinfunction "RED_LOW_RED_LOW") (pintype "passive"))
      (node (ref "U1") (pin "12") (pinfunction "LED6_12") (pintype "bidirectional"))
    )
    (net (code "72") (name "Net-(U1-LED7)") (class "Default")
      (node (ref "LED2") (pin "GREEN_LOW") (pinfunction "GREEN_LOW_GREEN_LOW") (pintype "passive"))
      (node (ref "U1") (pin "13") (pinfunction "LED7_13") (pintype "bidirectional"))
    )
    (net (code "73") (name "Net-(U1-LED8)") (class "Default")
      (node (ref "LED4") (pin "BLUE_LOW") (pinfunction "BLUE_LOW_BLUE_LOW") (pintype "passive"))
      (node (ref "U1") (pin "15") (pinfunction "LED8_15") (pintype "bidirectional"))
    )
    (net (code "74") (name "Net-(U1-LED9)") (class "Default")
      (node (ref "LED4") (pin "GREEN_LOW") (pinfunction "GREEN_LOW_GREEN_LOW") (pintype "passive"))
      (node (ref "U1") (pin "16") (pinfunction "LED9_16") (pintype "bidirectional"))
    )
    (net (code "75") (name "Net-(U1-LED10)") (class "Default")
      (node (ref "LED4") (pin "RED_LOW") (pinfunction "RED_LOW_RED_LOW") (pintype "passive"))
      (node (ref "U1") (pin "17") (pinfunction "LED10_17") (pintype "bidirectional"))
    )
    (net (code "76") (name "Net-(U1-LED11)") (class "Default")
      (node (ref "LED3") (pin "BLUE_LOW") (pinfunction "BLUE_LOW_BLUE_LOW") (pintype "passive"))
      (node (ref "U1") (pin "18") (pinfunction "LED11_18") (pintype "bidirectional"))
    )
    (net (code "77") (name "Net-(U1-LED12)") (class "Default")
      (node (ref "LED3") (pin "GREEN_LOW") (pinfunction "GREEN_LOW_GREEN_LOW") (pintype "passive"))
      (node (ref "U1") (pin "19") (pinfunction "LED12_19") (pintype "bidirectional"))
    )
    (net (code "78") (name "Net-(U1-LED13)") (class "Default")
      (node (ref "LED3") (pin "RED_LOW") (pinfunction "RED_LOW_RED_LOW") (pintype "passive"))
      (node (ref "U1") (pin "20") (pinfunction "LED13_20") (pintype "bidirectional"))
    )
    (net (code "79") (name "Net-(U1-LED14)") (class "Default")
      (node (ref "LED2") (pin "BLUE_LOW") (pinfunction "BLUE_LOW_BLUE_LOW") (pintype "passive"))
      (node (ref "U1") (pin "21") (pinfunction "LED14_21") (pintype "bidirectional"))
    )
    (net (code "80") (name "Net-(U2-LED0)") (class "Default")
      (node (ref "LED5") (pin "RED_LOW") (pinfunction "RED_LOW_RED_LOW") (pintype "passive"))
      (node (ref "U2") (pin "6") (pinfunction "LED0_6") (pintype "bidirectional"))
    )
    (net (code "81") (name "Net-(U2-LED1)") (class "Default")
      (node (ref "LED5") (pin "GREEN_LOW") (pinfunction "GREEN_LOW_GREEN_LOW") (pintype "passive"))
      (node (ref "U2") (pin "7") (pinfunction "LED1_7") (pintype "bidirectional"))
    )
    (net (code "82") (name "Net-(U2-LED2)") (class "Default")
      (node (ref "LED5") (pin "BLUE_LOW") (pinfunction "BLUE_LOW_BLUE_LOW") (pintype "passive"))
      (node (ref "U2") (pin "8") (pinfunction "LED2_8") (pintype "bidirectional"))
    )
    (net (code "83") (name "Net-(U2-LED3)") (class "Default")
      (node (ref "LED6") (pin "RED_LOW") (pinfunction "RED_LOW_RED_LOW") (pintype "passive"))
      (node (ref "U2") (pin "9") (pinfunction "LED3_9") (pintype "bidirectional"))
    )
    (net (code "84") (name "Net-(U2-LED4)") (class "Default")
      (node (ref "LED6") (pin "GREEN_LOW") (pinfunction "GREEN_LOW_GREEN_LOW") (pintype "passive"))
      (node (ref "U2") (pin "10") (pinfunction "LED4_10") (pintype "bidirectional"))
    )
    (net (code "85") (name "Net-(U2-LED5)") (class "Default")
      (node (ref "LED6") (pin "BLUE_LOW") (pinfunction "BLUE_LOW_BLUE_LOW") (pintype "passive"))
      (node (ref "U2") (pin "11") (pinfunction "LED5_11") (pintype "bidirectional"))
    )
    (net (code "86") (name "Net-(U2-LED6)") (class "Default")
      (node (ref "LED7") (pin "RED_LOW") (pinfunction "RED_LOW_RED_LOW") (pintype "passive"))
      (node (ref "U2") (pin "12") (pinfunction "LED6_12") (pintype "bidirectional"))
    )
    (net (code "87") (name "Net-(U2-LED7)") (class "Default")
      (node (ref "LED7") (pin "GREEN_LOW") (pinfunction "GREEN_LOW_GREEN_LOW") (pintype "passive"))
      (node (ref "U2") (pin "13") (pinfunction "LED7_13") (pintype "bidirectional"))
    )
    (net (code "88") (name "Net-(U2-LED8)") (class "Default")
      (node (ref "LED9") (pin "BLUE_LOW") (pinfunction "BLUE_LOW_BLUE_LOW") (pintype "passive"))
      (node (ref "U2") (pin "15") (pinfunction "LED8_15") (pintype "bidirectional"))
    )
    (net (code "89") (name "Net-(U2-LED9)") (class "Default")
      (node (ref "LED9") (pin "GREEN_LOW") (pinfunction "GREEN_LOW_GREEN_LOW") (pintype "passive"))
      (node (ref "U2") (pin "16") (pinfunction "LED9_16") (pintype "bidirectional"))
    )
    (net (code "90") (name "Net-(U2-LED10)") (class "Default")
      (node (ref "LED9") (pin "RED_LOW") (pinfunction "RED_LOW_RED_LOW") (pintype "passive"))
      (node (ref "U2") (pin "17") (pinfunction "LED10_17") (pintype "bidirectional"))
    )
    (net (code "91") (name "Net-(U2-LED11)") (class "Default")
      (node (ref "LED8") (pin "BLUE_LOW") (pinfunction "BLUE_LOW_BLUE_LOW") (pintype "passive"))
      (node (ref "U2") (pin "18") (pinfunction "LED11_18") (pintype "bidirectional"))
    )
    (net (code "92") (name "Net-(U2-LED12)") (class "Default")
      (node (ref "LED8") (pin "GREEN_LOW") (pinfunction "GREEN_LOW_GREEN_LOW") (pintype "passive"))
      (node (ref "U2") (pin "19") (pinfunction "LED12_19") (pintype "bidirectional"))
    )
    (net (code "93") (name "Net-(U2-LED13)") (class "Default")
      (node (ref "LED8") (pin "RED_LOW") (pinfunction "RED_LOW_RED_LOW") (pintype "passive"))
      (node (ref "U2") (pin "20") (pinfunction "LED13_20") (pintype "bidirectional"))
    )
    (net (code "94") (name "Net-(U2-LED14)") (class "Default")
      (node (ref "LED7") (pin "BLUE_LOW") (pinfunction "BLUE_LOW_BLUE_LOW") (pintype "passive"))
      (node (ref "U2") (pin "21") (pinfunction "LED14_21") (pintype "bidirectional"))
    )
    (net (code "95") (name "Net-(U3-LED0)") (class "Default")
      (node (ref "LED10") (pin "RED_LOW") (pinfunction "RED_LOW_RED_LOW") (pintype "passive"))
      (node (ref "U3") (pin "6") (pinfunction "LED0_6") (pintype "bidirectional"))
    )
    (net (code "96") (name "Net-(U3-LED1)") (class "Default")
      (node (ref "LED10") (pin "GREEN_LOW") (pinfunction "GREEN_LOW_GREEN_LOW") (pintype "passive"))
      (node (ref "U3") (pin "7") (pinfunction "LED1_7") (pintype "bidirectional"))
    )
    (net (code "97") (name "Net-(U3-LED2)") (class "Default")
      (node (ref "LED10") (pin "BLUE_LOW") (pinfunction "BLUE_LOW_BLUE_LOW") (pintype "passive"))
      (node (ref "U3") (pin "8") (pinfunction "LED2_8") (pintype "bidirectional"))
    )
    (net (code "98") (name "Net-(U3-LED3)") (class "Default")
      (node (ref "LED11") (pin "RED_LOW") (pinfunction "RED_LOW_RED_LOW") (pintype "passive"))
      (node (ref "U3") (pin "9") (pinfunction "LED3_9") (pintype "bidirectional"))
    )
    (net (code "99") (name "Net-(U3-LED4)") (class "Default")
      (node (ref "LED11") (pin "GREEN_LOW") (pinfunction "GREEN_LOW_GREEN_LOW") (pintype "passive"))
      (node (ref "U3") (pin "10") (pinfunction "LED4_10") (pintype "bidirectional"))
    )
    (net (code "100") (name "Net-(U3-LED5)") (class "Default")
      (node (ref "LED11") (pin "BLUE_LOW") (pinfunction "BLUE_LOW_BLUE_LOW") (pintype "passive"))
      (node (ref "U3") (pin "11") (pinfunction "LED5_11") (pintype "bidirectional"))
    )
    (net (code "101") (name "Net-(U3-LED6)") (class "Default")
      (node (ref "LED12") (pin "RED_LOW") (pinfunction "RED_LOW_RED_LOW") (pintype "passive"))
      (node (ref "U3") (pin "12") (pinfunction "LED6_12") (pintype "bidirectional"))
    )
    (net (code "102") (name "Net-(U3-LED7)") (class "Default")
      (node (ref "LED12") (pin "GREEN_LOW") (pinfunction "GREEN_LOW_GREEN_LOW") (pintype "passive"))
      (node (ref "U3") (pin "13") (pinfunction "LED7_13") (pintype "bidirectional"))
    )
    (net (code "103") (name "Net-(U3-LED8)") (class "Default")
      (node (ref "LED14") (pin "BLUE_LOW") (pinfunction "BLUE_LOW_BLUE_LOW") (pintype "passive"))
      (node (ref "U3") (pin "15") (pinfunction "LED8_15") (pintype "bidirectional"))
    )
    (net (code "104") (name "Net-(U3-LED9)") (class "Default")
      (node (ref "LED14") (pin "GREEN_LOW") (pinfunction "GREEN_LOW_GREEN_LOW") (pintype "passive"))
      (node (ref "U3") (pin "16") (pinfunction "LED9_16") (pintype "bidirectional"))
    )
    (net (code "105") (name "Net-(U3-LED10)") (class "Default")
      (node (ref "LED14") (pin "RED_LOW") (pinfunction "RED_LOW_RED_LOW") (pintype "passive"))
      (node (ref "U3") (pin "17") (pinfunction "LED10_17") (pintype "bidirectional"))
    )
    (net (code "106") (name "Net-(U3-LED11)") (class "Default")
      (node (ref "LED13") (pin "BLUE_LOW") (pinfunction "BLUE_LOW_BLUE_LOW") (pintype "passive"))
      (node (ref "U3") (pin "18") (pinfunction "LED11_18") (pintype "bidirectional"))
    )
    (net (code "107") (name "Net-(U3-LED12)") (class "Default")
      (node (ref "LED13") (pin "GREEN_LOW") (pinfunction "GREEN_LOW_GREEN_LOW") (pintype "passive"))
      (node (ref "U3") (pin "19") (pinfunction "LED12_19") (pintype "bidirectional"))
    )
    (net (code "108") (name "Net-(U3-LED13)") (class "Default")
      (node (ref "LED13") (pin "RED_LOW") (pinfunction "RED_LOW_RED_LOW") (pintype "passive"))
      (node (ref "U3") (pin "20") (pinfunction "LED13_20") (pintype "bidirectional"))
    )
    (net (code "109") (name "Net-(U3-LED14)") (class "Default")
      (node (ref "LED12") (pin "BLUE_LOW") (pinfunction "BLUE_LOW_BLUE_LOW") (pintype "passive"))
      (node (ref "U3") (pin "21") (pinfunction "LED14_21") (pintype "bidirectional"))
    )
    (net (code "110") (name "Net-(U4-LED0)") (class "Default")
      (node (ref "LED15") (pin "RED_LOW") (pinfunction "RED_LOW_RED_LOW") (pintype "passive"))
      (node (ref "U4") (pin "6") (pinfunction "LED0_6") (pintype "bidirectional"))
    )
    (net (code "111") (name "Net-(U4-LED1)") (class "Default")
      (node (ref "LED15") (pin "GREEN_LOW") (pinfunction "GREEN_LOW_GREEN_LOW") (pintype "passive"))
      (node (ref "U4") (pin "7") (pinfunction "LED1_7") (pintype "bidirectional"))
    )
    (net (code "112") (name "Net-(U4-LED2)") (class "Default")
      (node (ref "LED15") (pin "BLUE_LOW") (pinfunction "BLUE_LOW_BLUE_LOW") (pintype "passive"))
      (node (ref "U4") (pin "8") (pinfunction "LED2_8") (pintype "bidirectional"))
    )
    (net (code "113") (name "Net-(U4-LED3)") (class "Default")
      (node (ref "LED16") (pin "RED_LOW") (pinfunction "RED_LOW_RED_LOW") (pintype "passive"))
      (node (ref "U4") (pin "9") (pinfunction "LED3_9") (pintype "bidirectional"))
    )
    (net (code "114") (name "Net-(U4-LED4)") (class "Default")
      (node (ref "LED16") (pin "GREEN_LOW") (pinfunction "GREEN_LOW_GREEN_LOW") (pintype "passive"))
      (node (ref "U4") (pin "10") (pinfunction "LED4_10") (pintype "bidirectional"))
    )
    (net (code "115") (name "Net-(U4-LED5)") (class "Default")
      (node (ref "LED16") (pin "BLUE_LOW") (pinfunction "BLUE_LOW_BLUE_LOW") (pintype "passive"))
      (node (ref "U4") (pin "11") (pinfunction "LED5_11") (pintype "bidirectional"))
    )
    (net (code "116") (name "Net-(U4-LED6)") (class "Default")
      (node (ref "LED17") (pin "RED_LOW") (pinfunction "RED_LOW_RED_LOW") (pintype "passive"))
      (node (ref "U4") (pin "12") (pinfunction "LED6_12") (pintype "bidirectional"))
    )
    (net (code "117") (name "Net-(U4-LED7)") (class "Default")
      (node (ref "LED17") (pin "GREEN_LOW") (pinfunction "GREEN_LOW_GREEN_LOW") (pintype "passive"))
      (node (ref "U4") (pin "13") (pinfunction "LED7_13") (pintype "bidirectional"))
    )
    (net (code "118") (name "Net-(U4-LED8)") (class "Default")
      (node (ref "LED19") (pin "BLUE_LOW") (pinfunction "BLUE_LOW_BLUE_LOW") (pintype "passive"))
      (node (ref "U4") (pin "15") (pinfunction "LED8_15") (pintype "bidirectional"))
    )
    (net (code "119") (name "Net-(U4-LED9)") (class "Default")
      (node (ref "LED19") (pin "GREEN_LOW") (pinfunction "GREEN_LOW_GREEN_LOW") (pintype "passive"))
      (node (ref "U4") (pin "16") (pinfunction "LED9_16") (pintype "bidirectional"))
    )
    (net (code "120") (name "Net-(U4-LED10)") (class "Default")
      (node (ref "LED19") (pin "RED_LOW") (pinfunction "RED_LOW_RED_LOW") (pintype "passive"))
      (node (ref "U4") (pin "17") (pinfunction "LED10_17") (pintype "bidirectional"))
    )
    (net (code "121") (name "Net-(U4-LED11)") (class "Default")
      (node (ref "LED18") (pin "BLUE_LOW") (pinfunction "BLUE_LOW_BLUE_LOW") (pintype "passive"))
      (node (ref "U4") (pin "18") (pinfunction "LED11_18") (pintype "bidirectional"))
    )
    (net (code "122") (name "Net-(U4-LED12)") (class "Default")
      (node (ref "LED18") (pin "GREEN_LOW") (pinfunction "GREEN_LOW_GREEN_LOW") (pintype "passive"))
      (node (ref "U4") (pin "19") (pinfunction "LED12_19") (pintype "bidirectional"))
    )
    (net (code "123") (name "Net-(U4-LED13)") (class "Default")
      (node (ref "LED18") (pin "RED_LOW") (pinfunction "RED_LOW_RED_LOW") (pintype "passive"))
      (node (ref "U4") (pin "20") (pinfunction "LED13_20") (pintype "bidirectional"))
    )
    (net (code "124") (name "Net-(U4-LED14)") (class "Default")
      (node (ref "LED17") (pin "BLUE_LOW") (pinfunction "BLUE_LOW_BLUE_LOW") (pintype "passive"))
      (node (ref "U4") (pin "21") (pinfunction "LED14_21") (pintype "bidirectional"))
    )
    (net (code "125") (name "unconnected-(U1-LED15-Pad22)") (class "Default")
      (node (ref "U1") (pin "22") (pinfunction "LED15_22") (pintype "bidirectional"))
    )
    (net (code "126") (name "unconnected-(U2-LED15-Pad22)") (class "Default")
      (node (ref "U2") (pin "22") (pinfunction "LED15_22") (pintype "bidirectional"))
    )
    (net (code "127") (name "unconnected-(U3-LED15-Pad22)") (class "Default")
      (node (ref "U3") (pin "22") (pinfunction "LED15_22") (pintype "bidirectional"))
    )
    (net (code "128") (name "unconnected-(U4-LED15-Pad22)") (class "Default")
      (node (ref "U4") (pin "22") (pinfunction "LED15_22") (pintype "bidirectional"))
    )
  )
)
